# bitraf-bylarm-synth.net
KiCad netlist of a schematic drawn in EAGLE
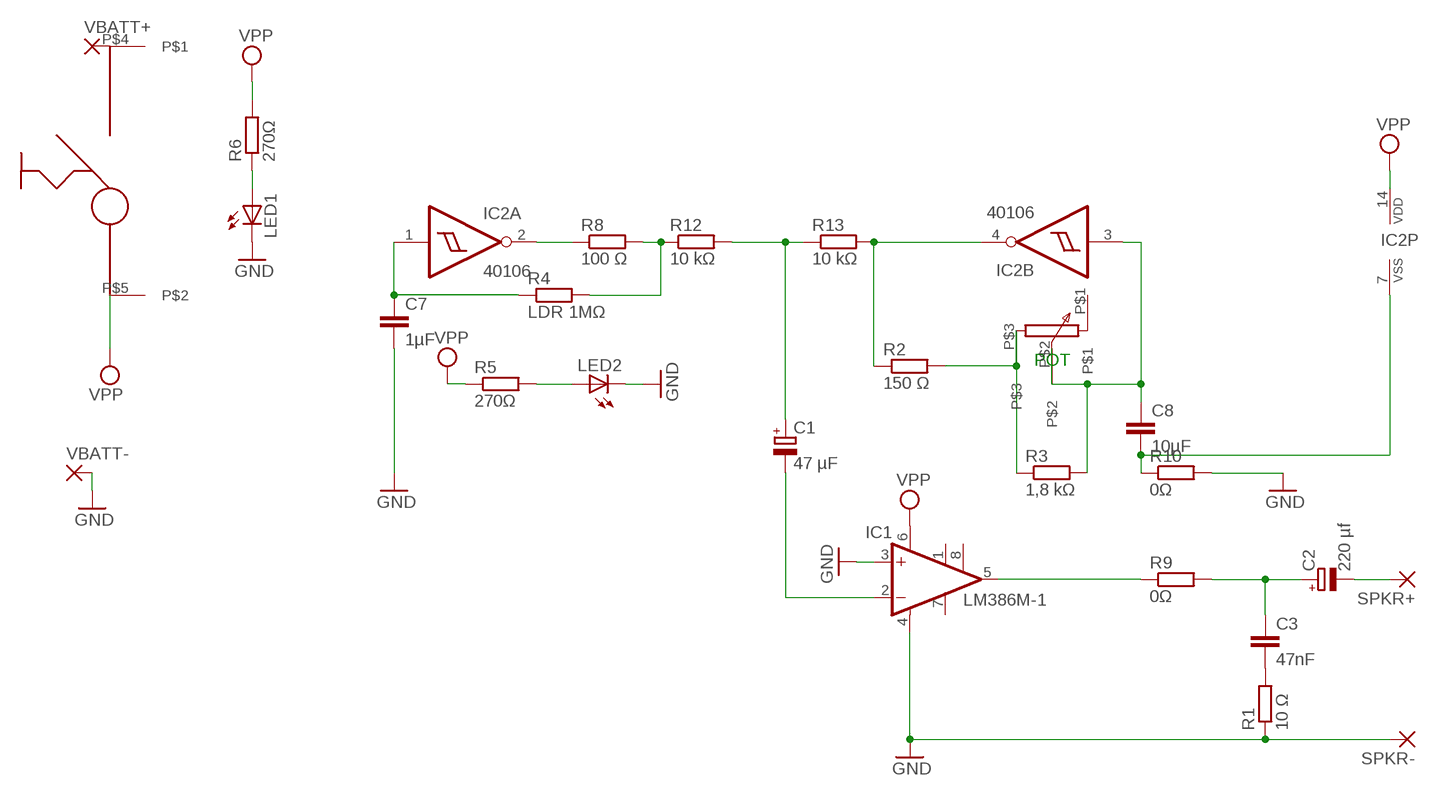
[diagram p0: schematic, sheet 1]

(export (version "E")
  (design (tool "Eeschema 10.0.6"))
  (components
    (comp (ref "C1")
      (value "47 µF")
      (footprint "eagle-import:153CLV-0605")
      (libsource (lib "eagle-import") (part "CPOL-EU153CLV-0605"))
    )
    (comp (ref "C2")
      (value "220 µf")
      (footprint "eagle-import:153CLV-0605")
      (libsource (lib "eagle-import") (part "CPOL-EU153CLV-0605"))
    )
    (comp (ref "C3")
      (value "47nF")
      (footprint "eagle-import:C0402")
      (libsource (lib "eagle-import") (part "C-EUC0402"))
    )
    (comp (ref "C7")
      (value "1µF")
      (footprint "eagle-import:C0603")
      (libsource (lib "eagle-import") (part "C-EUC0603"))
    )
    (comp (ref "C8")
      (value "10µF")
      (footprint "eagle-import:C1206")
      (libsource (lib "eagle-import") (part "C-EUC1206"))
    )
    (comp (ref "IC1")
      (value "LM386M-1")
      (footprint "eagle-import:SO08")
      (libsource (lib "eagle-import") (part "LM386?-M1"))
    )
    (comp (ref "IC2")
      (value "40106")
      (footprint "eagle-import:SO14")
      (libsource (lib "eagle-import") (part "40106D"))
    )
    (comp (ref "LED1")
      (value "LED3MM")
      (footprint "eagle-import:LED3MM")
      (libsource (lib "eagle-import") (part "LED3MM"))
    )
    (comp (ref "LED2")
      (value "LEDP-LCC-2")
      (footprint "eagle-import:P-LCC-2")
      (libsource (lib "eagle-import") (part "LEDP-LCC-2"))
    )
    (comp (ref "R1")
      (value "10 Ω")
      (footprint "eagle-import:R2512")
      (libsource (lib "eagle-import") (part "R-EU_R2512"))
    )
    (comp (ref "R2")
      (value "150 Ω")
      (footprint "eagle-import:R1206")
      (libsource (lib "eagle-import") (part "R-EU_R1206"))
    )
    (comp (ref "R3")
      (value "1,8 kΩ")
      (footprint "eagle-import:R1206")
      (libsource (lib "eagle-import") (part "R-EU_R1206"))
    )
    (comp (ref "R4")
      (value "LDR 1MΩ")
      (footprint "eagle-import:0204V")
      (libsource (lib "eagle-import") (part "R-EU_0204/2V"))
    )
    (comp (ref "R5")
      (value "270Ω")
      (footprint "eagle-import:R2512")
      (libsource (lib "eagle-import") (part "R-EU_R2512"))
    )
    (comp (ref "R6")
      (value "270Ω")
      (footprint "eagle-import:R2512")
      (libsource (lib "eagle-import") (part "R-EU_R2512"))
    )
    (comp (ref "R8")
      (value "100 Ω")
      (footprint "eagle-import:R1206")
      (libsource (lib "eagle-import") (part "R-EU_R1206"))
    )
    (comp (ref "R9")
      (value "0Ω")
      (footprint "eagle-import:R1206")
      (libsource (lib "eagle-import") (part "R-EU_R1206"))
    )
    (comp (ref "R10")
      (value "0Ω")
      (footprint "eagle-import:R1206")
      (libsource (lib "eagle-import") (part "R-EU_R1206"))
    )
    (comp (ref "R12")
      (value "10 kΩ")
      (footprint "eagle-import:R1206")
      (libsource (lib "eagle-import") (part "R-EU_R1206"))
    )
    (comp (ref "R13")
      (value "10 kΩ")
      (footprint "eagle-import:R1206")
      (libsource (lib "eagle-import") (part "R-EU_R1206"))
    )
    (comp (ref "SPKR+")
      (value "1,6/0,9")
      (footprint "eagle-import:1,6_0,9")
      (libsource (lib "eagle-import") (part "1,6/0,9"))
    )
    (comp (ref "SPKR-")
      (value "1,6/0,9")
      (footprint "eagle-import:1,6_0,9")
      (libsource (lib "eagle-import") (part "1,6/0,9"))
    )
    (comp (ref "U$1")
      (value "SMALLPOT")
      (footprint "eagle-import:SMALLPOT")
      (libsource (lib "eagle-import") (part "SMALLPOT"))
    )
    (comp (ref "U$2")
      (value "BYLARMSWITCH")
      (footprint "eagle-import:BYLARMSWITCH")
      (libsource (lib "eagle-import") (part "BYLARMSWITCH"))
    )
    (comp (ref "VBATT+")
      (value "2,15/1,0")
      (footprint "eagle-import:2,15_1,0")
      (libsource (lib "eagle-import") (part "2,15/1,0"))
    )
    (comp (ref "VBATT-")
      (value "2,15/1,0")
      (footprint "eagle-import:2,15_1,0")
      (libsource (lib "eagle-import") (part "2,15/1,0"))
    )
  )
  (nets
    (net (code "1") (name "GND") (class "Default")
      (node (ref "C7") (pin "2") (pinfunction "2_2") (pintype "passive"))
      (node (ref "IC1") (pin "3") (pinfunction "+IN_3") (pintype "input"))
      (node (ref "IC1") (pin "4") (pinfunction "GND_4") (pintype "power_in"))
      (node (ref "LED1") (pin "K") (pinfunction "C_K") (pintype "passive"))
      (node (ref "LED2") (pin "C") (pinfunction "C_C") (pintype "passive"))
      (node (ref "R1") (pin "1") (pinfunction "1_1") (pintype "passive"))
      (node (ref "R10") (pin "2") (pinfunction "2_2") (pintype "passive"))
      (node (ref "SPKR-") (pin "1") (pinfunction "P_1") (pintype "passive"))
      (node (ref "VBATT-") (pin "1") (pinfunction "P_1") (pintype "passive"))
    )
    (net (code "2") (name "Net-(C1-Pad+)") (class "Default")
      (node (ref "C1") (pin "+") (pinfunction "+_+") (pintype "passive"))
      (node (ref "R12") (pin "2") (pinfunction "2_2") (pintype "passive"))
      (node (ref "R13") (pin "1") (pinfunction "1_1") (pintype "passive"))
    )
    (net (code "3") (name "Net-(C2-Pad+)") (class "Default")
      (node (ref "C2") (pin "+") (pinfunction "+_+") (pintype "passive"))
      (node (ref "C3") (pin "1") (pinfunction "1_1") (pintype "passive"))
      (node (ref "R9") (pin "2") (pinfunction "2_2") (pintype "passive"))
    )
    (net (code "4") (name "Net-(C3-Pad2)") (class "Default")
      (node (ref "C3") (pin "2") (pinfunction "2_2") (pintype "passive"))
      (node (ref "R1") (pin "2") (pinfunction "2_2") (pintype "passive"))
    )
    (net (code "5") (name "Net-(IC1--IN)") (class "Default")
      (node (ref "C1") (pin "-") (pinfunction "-_-") (pintype "passive"))
      (node (ref "IC1") (pin "2") (pinfunction "-IN_2") (pintype "input"))
    )
    (net (code "6") (name "Net-(IC1-OUT)") (class "Default")
      (node (ref "IC1") (pin "5") (pinfunction "OUT_5") (pintype "output"))
      (node (ref "R9") (pin "1") (pinfunction "1_1") (pintype "passive"))
    )
    (net (code "7") (name "Net-(IC2A-I)") (class "Default")
      (node (ref "C7") (pin "1") (pinfunction "1_1") (pintype "passive"))
      (node (ref "IC2") (pin "1") (pinfunction "I_1") (pintype "input"))
      (node (ref "R4") (pin "1") (pinfunction "1_1") (pintype "passive"))
    )
    (net (code "8") (name "Net-(IC2A-O)") (class "Default")
      (node (ref "IC2") (pin "2") (pinfunction "O_2") (pintype "output"))
      (node (ref "R8") (pin "1") (pinfunction "1_1") (pintype "passive"))
    )
    (net (code "9") (name "Net-(IC2B-I)") (class "Default")
      (node (ref "C8") (pin "1") (pinfunction "1_1") (pintype "passive"))
      (node (ref "IC2") (pin "3") (pinfunction "I_3") (pintype "input"))
      (node (ref "R3") (pin "2") (pinfunction "2_2") (pintype "passive"))
      (node (ref "U$1") (pin "P$2") (pinfunction "P$2_P$2") (pintype "bidirectional"))
    )
    (net (code "10") (name "Net-(IC2B-O)") (class "Default")
      (node (ref "IC2") (pin "4") (pinfunction "O_4") (pintype "output"))
      (node (ref "R13") (pin "2") (pinfunction "2_2") (pintype "passive"))
      (node (ref "R2") (pin "1") (pinfunction "1_1") (pintype "passive"))
    )
    (net (code "11") (name "Net-(IC2G-VSS)") (class "Default")
      (node (ref "C8") (pin "2") (pinfunction "2_2") (pintype "passive"))
      (node (ref "IC2") (pin "7") (pinfunction "VSS_7") (pintype "power_in"))
      (node (ref "R10") (pin "1") (pinfunction "1_1") (pintype "passive"))
    )
    (net (code "12") (name "Net-(LED1-PadA)") (class "Default")
      (node (ref "LED1") (pin "A") (pinfunction "A_A") (pintype "passive"))
      (node (ref "R6") (pin "1") (pinfunction "1_1") (pintype "passive"))
    )
    (net (code "13") (name "Net-(LED2-PadA)") (class "Default")
      (node (ref "LED2") (pin "A") (pinfunction "A_A") (pintype "passive"))
      (node (ref "R5") (pin "2") (pinfunction "2_2") (pintype "passive"))
    )
    (net (code "14") (name "Net-(R2-Pad2)") (class "Default")
      (node (ref "R2") (pin "2") (pinfunction "2_2") (pintype "passive"))
      (node (ref "R3") (pin "1") (pinfunction "1_1") (pintype "passive"))
      (node (ref "U$1") (pin "P$3") (pinfunction "P$3_P$3") (pintype "bidirectional"))
    )
    (net (code "15") (name "Net-(R12-Pad1)") (class "Default")
      (node (ref "R12") (pin "1") (pinfunction "1_1") (pintype "passive"))
      (node (ref "R4") (pin "2") (pinfunction "2_2") (pintype "passive"))
      (node (ref "R8") (pin "2") (pinfunction "2_2") (pintype "passive"))
    )
    (net (code "16") (name "Net-(SPKR+-P)") (class "Default")
      (node (ref "C2") (pin "-") (pinfunction "-_-") (pintype "passive"))
      (node (ref "SPKR+") (pin "1") (pinfunction "P_1") (pintype "passive"))
    )
    (net (code "17") (name "Net-(U$2-P$1)") (class "Default")
      (node (ref "U$2") (pin "P$4") (pinfunction "P$1_P$4") (pintype "bidirectional"))
      (node (ref "VBATT+") (pin "1") (pinfunction "P_1") (pintype "passive"))
    )
    (net (code "18") (name "VPP") (class "Default")
      (node (ref "IC1") (pin "6") (pinfunction "VS_6") (pintype "power_in"))
      (node (ref "IC2") (pin "14") (pinfunction "VDD_14") (pintype "power_in"))
      (node (ref "R5") (pin "1") (pinfunction "1_1") (pintype "passive"))
      (node (ref "R6") (pin "2") (pinfunction "2_2") (pintype "passive"))
      (node (ref "U$2") (pin "P$5") (pinfunction "P$2_P$5") (pintype "bidirectional"))
    )
    (net (code "19") (name "unconnected-(IC1-BYPASS-Pad7)") (class "Default")
      (node (ref "IC1") (pin "7") (pinfunction "BYPASS_7") (pintype "passive"))
    )
    (net (code "20") (name "unconnected-(IC1-GAIN-Pad1)") (class "Default")
      (node (ref "IC1") (pin "1") (pinfunction "GAIN_1") (pintype "passive"))
    )
    (net (code "21") (name "unconnected-(IC1-GAIN-Pad8)") (class "Default")
      (node (ref "IC1") (pin "8") (pinfunction "GAIN_8") (pintype "passive"))
    )
    (net (code "22") (name "unconnected-(U$1-PadP$1)") (class "Default")
      (node (ref "U$1") (pin "P$1") (pinfunction "P$1_P$1") (pintype "bidirectional"))
    )
  )
)
